# pmg001.net
KiCad netlist of a schematic drawn in EAGLE
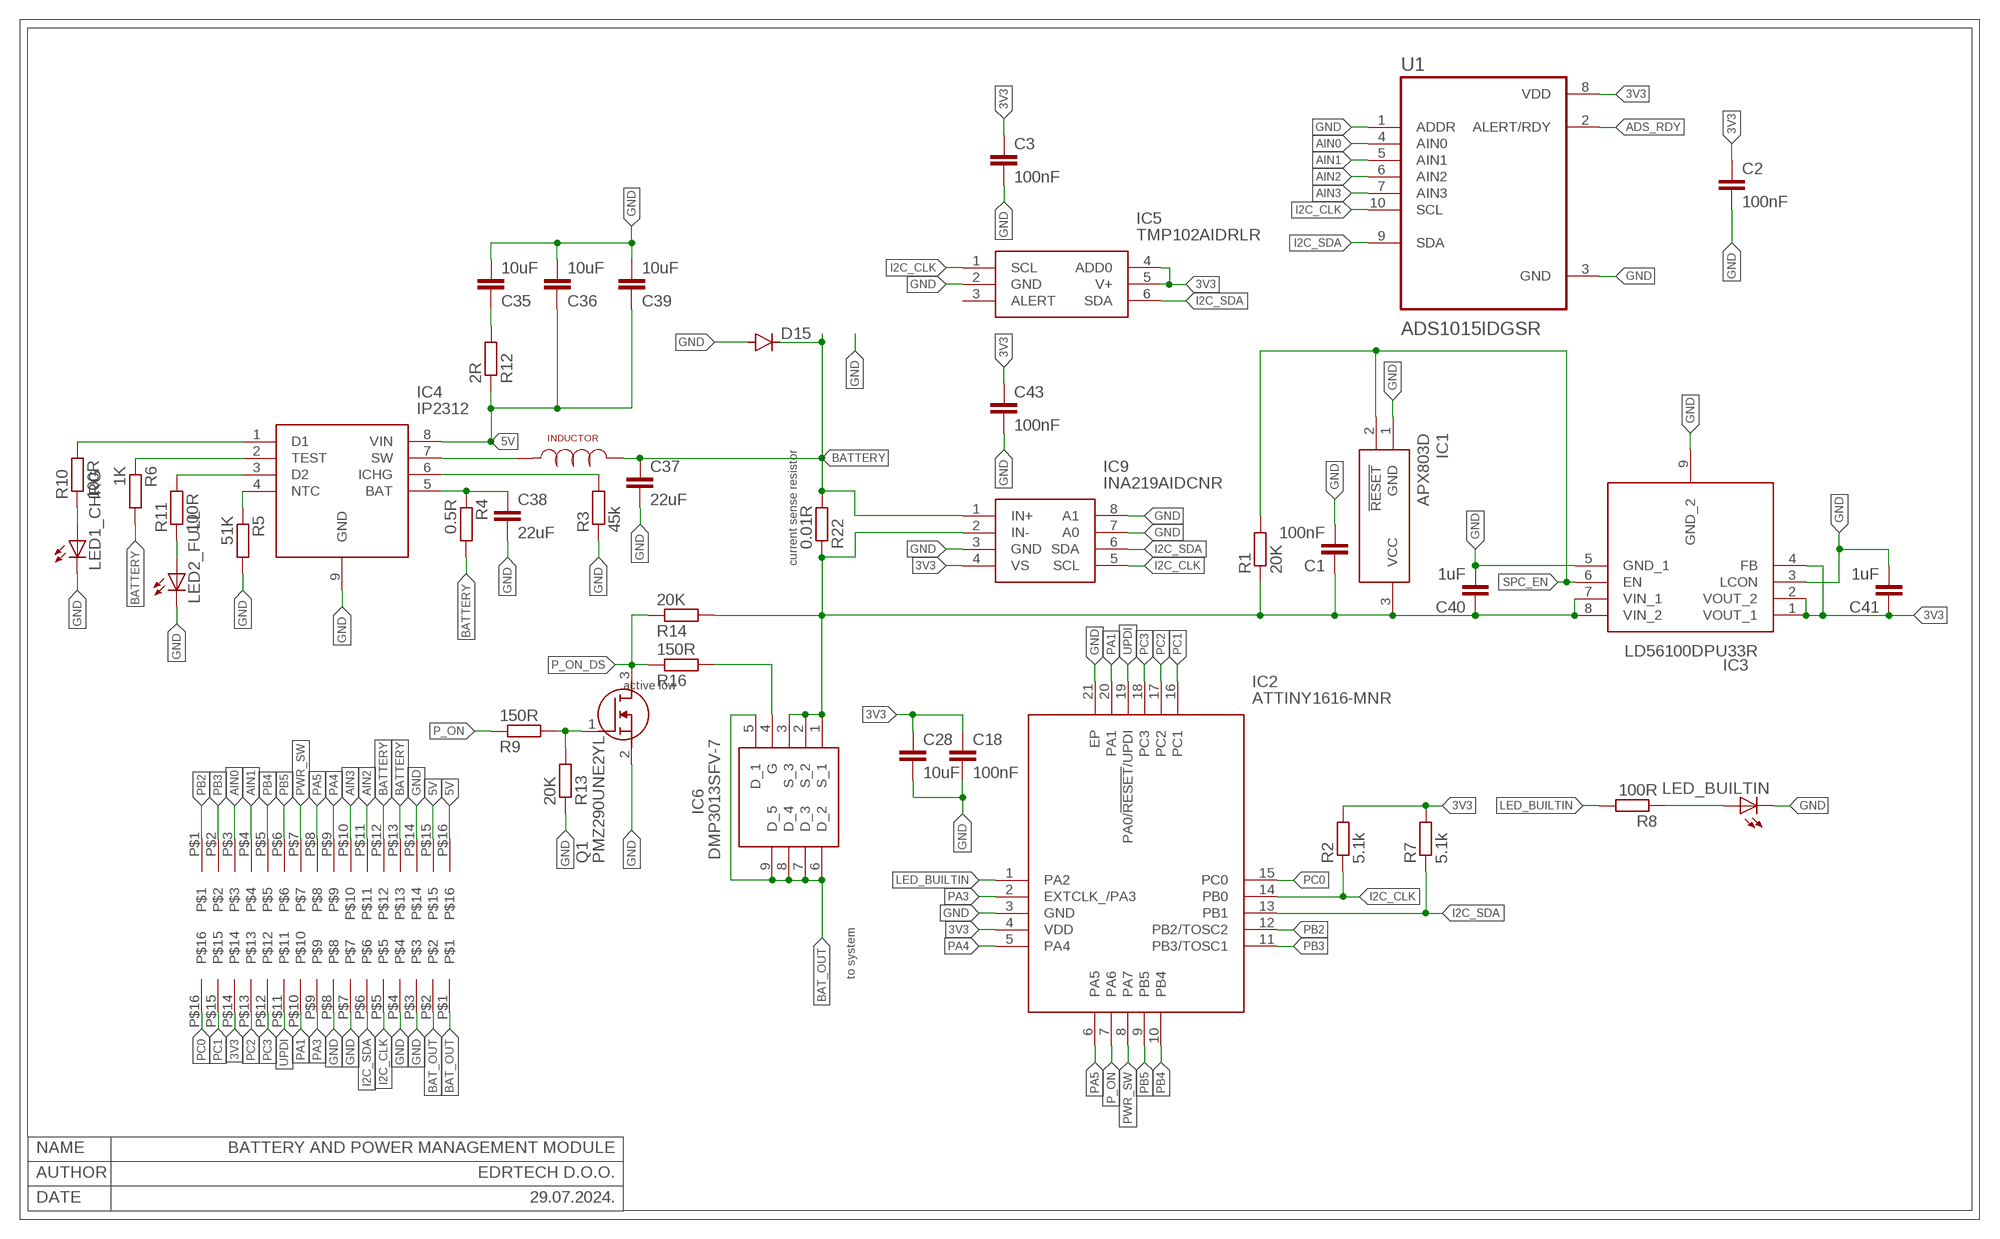
[diagram p0: schematic, sheet 1]

(export (version "E")
  (design (tool "Eeschema 10.0.6"))
  (components
    (comp (ref "C1")
      (value "100nF")
      (footprint "eagle-import:C0402")
      (libsource (lib "eagle-import") (part "C-EUC0402"))
    )
    (comp (ref "C2")
      (value "100nF")
      (footprint "eagle-import:C0402")
      (libsource (lib "eagle-import") (part "C-EUC0402"))
    )
    (comp (ref "C3")
      (value "100nF")
      (footprint "eagle-import:C0402")
      (libsource (lib "eagle-import") (part "C-EUC0402"))
    )
    (comp (ref "C18")
      (value "100nF")
      (footprint "eagle-import:C0402")
      (libsource (lib "eagle-import") (part "C-EUC0402"))
    )
    (comp (ref "C28")
      (value "10uF")
      (footprint "eagle-import:C0402")
      (libsource (lib "eagle-import") (part "C-EUC0402"))
    )
    (comp (ref "C35")
      (value "10uF")
      (footprint "eagle-import:C0603")
      (libsource (lib "eagle-import") (part "C-EUC0603"))
    )
    (comp (ref "C36")
      (value "10uF")
      (footprint "eagle-import:C0603")
      (libsource (lib "eagle-import") (part "C-EUC0603"))
    )
    (comp (ref "C37")
      (value "22uF")
      (footprint "eagle-import:C0603")
      (libsource (lib "eagle-import") (part "C-EUC0603"))
    )
    (comp (ref "C38")
      (value "22uF")
      (footprint "eagle-import:C0603")
      (libsource (lib "eagle-import") (part "C-EUC0603"))
    )
    (comp (ref "C39")
      (value "10uF")
      (footprint "eagle-import:C0603")
      (libsource (lib "eagle-import") (part "C-EUC0603"))
    )
    (comp (ref "C40")
      (value "1uF")
      (footprint "eagle-import:C0402")
      (libsource (lib "eagle-import") (part "C-EUC0402"))
    )
    (comp (ref "C41")
      (value "1uF")
      (footprint "eagle-import:C0402")
      (libsource (lib "eagle-import") (part "C-EUC0402"))
    )
    (comp (ref "C43")
      (value "100nF")
      (footprint "eagle-import:C0402")
      (libsource (lib "eagle-import") (part "C-EUC0402"))
    )
    (comp (ref "D15")
      (value "DIODE-SOD523")
      (footprint "eagle-import:SOD523")
      (libsource (lib "eagle-import") (part "DIODE-SOD523"))
    )
    (comp (ref "IC1")
      (value "APX803D-29SAG-7")
      (footprint "eagle-import:SOT96P240X110-3N")
      (fields (field (name "MOUSER_PART_NUMBER") "621-APX803D-29SAG-7"))
      (libsource (lib "eagle-import") (part "APX803D-29SAG-7"))
    )
    (comp (ref "IC2")
      (value "ATTINY1616-MNR")
      (footprint "eagle-import:QFN40P300X300X90-21N")
      (fields (field (name "MOUSER_PART_NUMBER") "556-ATTINY1616MNR"))
      (libsource (lib "eagle-import") (part "ATTINY1616-MNR"))
    )
    (comp (ref "IC3")
      (value "LD56100DPU30R")
      (footprint "eagle-import:SON40P120X160X50-9N")
      (fields (field (name "MOUSER_PART_NUMBER") "511-LD56100DPU30R"))
      (libsource (lib "eagle-import") (part "LD56100DPU30R"))
    )
    (comp (ref "IC4")
      (value "IP2312")
      (footprint "eagle-import:SOIC127P600X165-9N")
      (libsource (lib "eagle-import") (part "IP2312"))
    )
    (comp (ref "IC5")
      (value "TMP102AIDRLR")
      (footprint "eagle-import:SOTFL50P160X60-6N")
      (fields (field (name "MOUSER_PART_NUMBER") "595-TMP102AIDRLR"))
      (libsource (lib "eagle-import") (part "TMP102AIDRLR"))
    )
    (comp (ref "IC6")
      (value "DMP3013SFV-7")
      (footprint "eagle-import:DMP3036SFV7")
      (fields (field (name "MOUSER_PART_NUMBER") "621-DMP3013SFV-7"))
      (libsource (lib "eagle-import") (part "DMP3013SFV-7"))
    )
    (comp (ref "IC9")
      (value "INA219AIDCNR")
      (footprint "eagle-import:SOP65P280X145-8N")
      (fields (field (name "MOUSER_PART_NUMBER") "595-INA219AIDCNR"))
      (libsource (lib "eagle-import") (part "INA219AIDCNR"))
    )
    (comp (ref "LED1_CHRG")
      (value "LEDCHIPLED_0603")
      (footprint "eagle-import:CHIPLED_0603")
      (libsource (lib "eagle-import") (part "LEDCHIPLED_0603"))
    )
    (comp (ref "LED2_FULL")
      (value "LEDCHIPLED_0603")
      (footprint "eagle-import:CHIPLED_0603")
      (libsource (lib "eagle-import") (part "LEDCHIPLED_0603"))
    )
    (comp (ref "LED_BUILTIN")
      (value "LEDCHIPLED_0603")
      (footprint "eagle-import:CHIPLED_0603")
      (libsource (lib "eagle-import") (part "LEDCHIPLED_0603"))
    )
    (comp (ref "Q1")
      (value "PMZ290UNE2YL")
      (footprint "eagle-import:PMZ290UNE2YL")
      (fields (field (name "MOUSER_PART_NUMBER") "771-PMZ290UNE2YL"))
      (libsource (lib "eagle-import") (part "PMZ290UNE2YL"))
    )
    (comp (ref "R1")
      (value "20K")
      (footprint "eagle-import:R0402")
      (libsource (lib "eagle-import") (part "R-EU_R0402"))
    )
    (comp (ref "R2")
      (value "5.1k")
      (footprint "eagle-import:R0402")
      (libsource (lib "eagle-import") (part "R-EU_R0402"))
    )
    (comp (ref "R3")
      (value "45k")
      (footprint "eagle-import:R0402")
      (libsource (lib "eagle-import") (part "R-EU_R0402"))
    )
    (comp (ref "R4")
      (value "0.5R")
      (footprint "eagle-import:R0402")
      (libsource (lib "eagle-import") (part "R-EU_R0402"))
    )
    (comp (ref "R5")
      (value "51K")
      (footprint "eagle-import:R0402")
      (libsource (lib "eagle-import") (part "R-EU_R0402"))
    )
    (comp (ref "R6")
      (value "1K")
      (footprint "eagle-import:R0402")
      (libsource (lib "eagle-import") (part "R-EU_R0402"))
    )
    (comp (ref "R7")
      (value "5.1k")
      (footprint "eagle-import:R0402")
      (libsource (lib "eagle-import") (part "R-EU_R0402"))
    )
    (comp (ref "R8")
      (value "100R")
      (footprint "eagle-import:R0402")
      (libsource (lib "eagle-import") (part "R-EU_R0402"))
    )
    (comp (ref "R9")
      (value "150R")
      (footprint "eagle-import:R0402")
      (libsource (lib "eagle-import") (part "R-EU_R0402"))
    )
    (comp (ref "R10")
      (value "100R")
      (footprint "eagle-import:R0402")
      (libsource (lib "eagle-import") (part "R-EU_R0402"))
    )
    (comp (ref "R11")
      (value "100R")
      (footprint "eagle-import:R0402")
      (libsource (lib "eagle-import") (part "R-EU_R0402"))
    )
    (comp (ref "R12")
      (value "2R")
      (footprint "eagle-import:R0402")
      (libsource (lib "eagle-import") (part "R-EU_R0402"))
    )
    (comp (ref "R13")
      (value "20K")
      (footprint "eagle-import:R0402")
      (libsource (lib "eagle-import") (part "R-EU_R0402"))
    )
    (comp (ref "R14")
      (value "20K")
      (footprint "eagle-import:R0402")
      (libsource (lib "eagle-import") (part "R-EU_R0402"))
    )
    (comp (ref "R16")
      (value "150R")
      (footprint "eagle-import:R0402")
      (libsource (lib "eagle-import") (part "R-EU_R0402"))
    )
    (comp (ref "R22")
      (value "0.01R")
      (footprint "eagle-import:R2512")
      (libsource (lib "eagle-import") (part "R-EU_R2512"))
    )
    (comp (ref "U$1")
      (value "1.27_MALE_16P_HEADER")
      (footprint "eagle-import:1.27_MALE_16P_HEADER")
      (libsource (lib "eagle-import") (part "1.27_MALE_16P_HEADER"))
    )
    (comp (ref "U$2")
      (value "1.27_MALE_16P_HEADER")
      (footprint "eagle-import:1.27_MALE_16P_HEADER")
      (libsource (lib "eagle-import") (part "1.27_MALE_16P_HEADER"))
    )
    (comp (ref "U$91")
      (value "1uH")
      (footprint "eagle-import:NRS5040T3R3NMGJ")
      (libsource (lib "eagle-import") (part "NRS5040T3R3NMGJ"))
    )
    (comp (ref "U1")
      (value "ADS1015IDGSR")
      (footprint "eagle-import:SOP50P490X110-10N")
      (fields (field (name "MF") "Texas Instruments"))
      (libsource (lib "eagle-import") (part "ADS1015IDGSR"))
    )
  )
  (nets
    (net (code "1") (name "3V3") (class "Default")
      (node (ref "C18") (pin "1") (pinfunction "1_1") (pintype "passive"))
      (node (ref "C2") (pin "1") (pinfunction "1_1") (pintype "passive"))
      (node (ref "C28") (pin "1") (pinfunction "1_1") (pintype "passive"))
      (node (ref "C3") (pin "1") (pinfunction "1_1") (pintype "passive"))
      (node (ref "C41") (pin "1") (pinfunction "1_1") (pintype "passive"))
      (node (ref "C43") (pin "1") (pinfunction "1_1") (pintype "passive"))
      (node (ref "IC2") (pin "4") (pinfunction "VDD_4") (pintype "bidirectional"))
      (node (ref "IC3") (pin "1") (pinfunction "VOUT_1_1") (pintype "bidirectional"))
      (node (ref "IC3") (pin "2") (pinfunction "VOUT_2_2") (pintype "bidirectional"))
      (node (ref "IC3") (pin "4") (pinfunction "FB_4") (pintype "bidirectional"))
      (node (ref "IC5") (pin "4") (pinfunction "ADD0_4") (pintype "bidirectional"))
      (node (ref "IC5") (pin "5") (pinfunction "V+_5") (pintype "bidirectional"))
      (node (ref "IC9") (pin "4") (pinfunction "VS_4") (pintype "bidirectional"))
      (node (ref "R2") (pin "2") (pinfunction "2_2") (pintype "passive"))
      (node (ref "R7") (pin "2") (pinfunction "2_2") (pintype "passive"))
      (node (ref "U$2") (pin "P$14") (pinfunction "P$14_P$14") (pintype "bidirectional"))
      (node (ref "U1") (pin "8") (pinfunction "VDD_8") (pintype "power_in"))
    )
    (net (code "2") (name "5V") (class "Default")
      (node (ref "C36") (pin "1") (pinfunction "1_1") (pintype "passive"))
      (node (ref "C39") (pin "1") (pinfunction "1_1") (pintype "passive"))
      (node (ref "IC4") (pin "8") (pinfunction "VIN_8") (pintype "bidirectional"))
      (node (ref "R12") (pin "1") (pinfunction "1_1") (pintype "passive"))
      (node (ref "U$1") (pin "P$15") (pinfunction "P$15_P$15") (pintype "bidirectional"))
      (node (ref "U$1") (pin "P$16") (pinfunction "P$16_P$16") (pintype "bidirectional"))
    )
    (net (code "3") (name "ADS_RDY") (class "Default")
      (node (ref "U1") (pin "2") (pinfunction "ALERT/RDY_2") (pintype "output"))
    )
    (net (code "4") (name "AIN0") (class "Default")
      (node (ref "U$1") (pin "P$3") (pinfunction "P$3_P$3") (pintype "bidirectional"))
      (node (ref "U1") (pin "4") (pinfunction "AIN0_4") (pintype "input"))
    )
    (net (code "5") (name "AIN1") (class "Default")
      (node (ref "U$1") (pin "P$4") (pinfunction "P$4_P$4") (pintype "bidirectional"))
      (node (ref "U1") (pin "5") (pinfunction "AIN1_5") (pintype "input"))
    )
    (net (code "6") (name "AIN2") (class "Default")
      (node (ref "U$1") (pin "P$11") (pinfunction "P$11_P$11") (pintype "bidirectional"))
      (node (ref "U1") (pin "6") (pinfunction "AIN2_6") (pintype "input"))
    )
    (net (code "7") (name "AIN3") (class "Default")
      (node (ref "U$1") (pin "P$10") (pinfunction "P$10_P$10") (pintype "bidirectional"))
      (node (ref "U1") (pin "7") (pinfunction "AIN3_7") (pintype "input"))
    )
    (net (code "8") (name "BATTERY") (class "Default")
      (node (ref "C37") (pin "1") (pinfunction "1_1") (pintype "passive"))
      (node (ref "D15") (pin "C") (pinfunction "C_C") (pintype "passive"))
      (node (ref "IC9") (pin "1") (pinfunction "IN+_1") (pintype "bidirectional"))
      (node (ref "R22") (pin "2") (pinfunction "2_2") (pintype "passive"))
      (node (ref "R4") (pin "2") (pinfunction "2_2") (pintype "passive"))
      (node (ref "R6") (pin "2") (pinfunction "2_2") (pintype "passive"))
      (node (ref "U$1") (pin "P$12") (pinfunction "P$12_P$12") (pintype "bidirectional"))
      (node (ref "U$1") (pin "P$13") (pinfunction "P$13_P$13") (pintype "bidirectional"))
      (node (ref "U$91") (pin "P$1") (pinfunction "P$1_P$1") (pintype "bidirectional"))
    )
    (net (code "9") (name "BAT_OUT") (class "Default")
      (node (ref "IC6") (pin "5") (pinfunction "D_1_5") (pintype "bidirectional"))
      (node (ref "IC6") (pin "6") (pinfunction "D_2_6") (pintype "bidirectional"))
      (node (ref "IC6") (pin "7") (pinfunction "D_3_7") (pintype "bidirectional"))
      (node (ref "IC6") (pin "8") (pinfunction "D_4_8") (pintype "bidirectional"))
      (node (ref "IC6") (pin "9") (pinfunction "D_5_9") (pintype "bidirectional"))
      (node (ref "U$2") (pin "P$1") (pinfunction "P$1_P$1") (pintype "bidirectional"))
      (node (ref "U$2") (pin "P$2") (pinfunction "P$2_P$2") (pintype "bidirectional"))
    )
    (net (code "10") (name "GND") (class "Default")
      (node (ref "C1") (pin "2") (pinfunction "2_2") (pintype "passive"))
      (node (ref "C18") (pin "2") (pinfunction "2_2") (pintype "passive"))
      (node (ref "C2") (pin "2") (pinfunction "2_2") (pintype "passive"))
      (node (ref "C28") (pin "2") (pinfunction "2_2") (pintype "passive"))
      (node (ref "C3") (pin "2") (pinfunction "2_2") (pintype "passive"))
      (node (ref "C35") (pin "2") (pinfunction "2_2") (pintype "passive"))
      (node (ref "C36") (pin "2") (pinfunction "2_2") (pintype "passive"))
      (node (ref "C37") (pin "2") (pinfunction "2_2") (pintype "passive"))
      (node (ref "C38") (pin "2") (pinfunction "2_2") (pintype "passive"))
      (node (ref "C39") (pin "2") (pinfunction "2_2") (pintype "passive"))
      (node (ref "C40") (pin "2") (pinfunction "2_2") (pintype "passive"))
      (node (ref "C41") (pin "2") (pinfunction "2_2") (pintype "passive"))
      (node (ref "C43") (pin "2") (pinfunction "2_2") (pintype "passive"))
      (node (ref "D15") (pin "A") (pinfunction "A_A") (pintype "passive"))
      (node (ref "IC1") (pin "1") (pinfunction "GND_1") (pintype "bidirectional"))
      (node (ref "IC2") (pin "21") (pinfunction "EP_21") (pintype "bidirectional"))
      (node (ref "IC2") (pin "3") (pinfunction "GND_3") (pintype "bidirectional"))
      (node (ref "IC3") (pin "3") (pinfunction "LCON_3") (pintype "bidirectional"))
      (node (ref "IC3") (pin "5") (pinfunction "GND_1_5") (pintype "bidirectional"))
      (node (ref "IC3") (pin "9") (pinfunction "GND_2_9") (pintype "bidirectional"))
      (node (ref "IC4") (pin "9") (pinfunction "GND_9") (pintype "bidirectional"))
      (node (ref "IC5") (pin "2") (pinfunction "GND_2") (pintype "bidirectional"))
      (node (ref "IC9") (pin "3") (pinfunction "GND_3") (pintype "bidirectional"))
      (node (ref "IC9") (pin "7") (pinfunction "A0_7") (pintype "bidirectional"))
      (node (ref "IC9") (pin "8") (pinfunction "A1_8") (pintype "bidirectional"))
      (node (ref "LED1_CHRG") (pin "C") (pinfunction "C_C") (pintype "passive"))
      (node (ref "LED2_FULL") (pin "C") (pinfunction "C_C") (pintype "passive"))
      (node (ref "LED_BUILTIN") (pin "C") (pinfunction "C_C") (pintype "passive"))
      (node (ref "Q1") (pin "2") (pinfunction "S_2") (pintype "bidirectional"))
      (node (ref "R13") (pin "1") (pinfunction "1_1") (pintype "passive"))
      (node (ref "R3") (pin "1") (pinfunction "1_1") (pintype "passive"))
      (node (ref "R5") (pin "2") (pinfunction "2_2") (pintype "passive"))
      (node (ref "U$1") (pin "P$14") (pinfunction "P$14_P$14") (pintype "bidirectional"))
      (node (ref "U$2") (pin "P$3") (pinfunction "P$3_P$3") (pintype "bidirectional"))
      (node (ref "U$2") (pin "P$4") (pinfunction "P$4_P$4") (pintype "bidirectional"))
      (node (ref "U$2") (pin "P$7") (pinfunction "P$7_P$7") (pintype "bidirectional"))
      (node (ref "U$2") (pin "P$8") (pinfunction "P$8_P$8") (pintype "bidirectional"))
      (node (ref "U1") (pin "1") (pinfunction "ADDR_1") (pintype "input"))
      (node (ref "U1") (pin "3") (pinfunction "GND_3") (pintype "power_in"))
    )
    (net (code "11") (name "I2C_CLK") (class "Default")
      (node (ref "IC2") (pin "14") (pinfunction "PB0_14") (pintype "bidirectional"))
      (node (ref "IC5") (pin "1") (pinfunction "SCL_1") (pintype "bidirectional"))
      (node (ref "IC9") (pin "5") (pinfunction "SCL_5") (pintype "bidirectional"))
      (node (ref "R2") (pin "1") (pinfunction "1_1") (pintype "passive"))
      (node (ref "U$2") (pin "P$5") (pinfunction "P$5_P$5") (pintype "bidirectional"))
      (node (ref "U1") (pin "10") (pinfunction "SCL_10") (pintype "input"))
    )
    (net (code "12") (name "I2C_SDA") (class "Default")
      (node (ref "IC2") (pin "13") (pinfunction "PB1_13") (pintype "bidirectional"))
      (node (ref "IC5") (pin "6") (pinfunction "SDA_6") (pintype "bidirectional"))
      (node (ref "IC9") (pin "6") (pinfunction "SDA_6") (pintype "bidirectional"))
      (node (ref "R7") (pin "1") (pinfunction "1_1") (pintype "passive"))
      (node (ref "U$2") (pin "P$6") (pinfunction "P$6_P$6") (pintype "bidirectional"))
      (node (ref "U1") (pin "9") (pinfunction "SDA_9") (pintype "bidirectional"))
    )
    (net (code "13") (name "LED_BUILTIN") (class "Default")
      (node (ref "IC2") (pin "1") (pinfunction "PA2_1") (pintype "bidirectional"))
      (node (ref "R8") (pin "2") (pinfunction "2_2") (pintype "passive"))
    )
    (net (code "14") (name "Net-(C35-Pad1)") (class "Default")
      (node (ref "C35") (pin "1") (pinfunction "1_1") (pintype "passive"))
      (node (ref "R12") (pin "2") (pinfunction "2_2") (pintype "passive"))
    )
    (net (code "15") (name "Net-(IC1-VCC)") (class "Default")
      (node (ref "C1") (pin "1") (pinfunction "1_1") (pintype "passive"))
      (node (ref "C40") (pin "1") (pinfunction "1_1") (pintype "passive"))
      (node (ref "IC1") (pin "3") (pinfunction "VCC_3") (pintype "bidirectional"))
      (node (ref "IC3") (pin "7") (pinfunction "VIN_1_7") (pintype "bidirectional"))
      (node (ref "IC3") (pin "8") (pinfunction "VIN_2_8") (pintype "bidirectional"))
      (node (ref "IC6") (pin "1") (pinfunction "S_1_1") (pintype "bidirectional"))
      (node (ref "IC6") (pin "2") (pinfunction "S_2_2") (pintype "bidirectional"))
      (node (ref "IC6") (pin "3") (pinfunction "S_3_3") (pintype "bidirectional"))
      (node (ref "IC9") (pin "2") (pinfunction "IN-_2") (pintype "bidirectional"))
      (node (ref "R1") (pin "1") (pinfunction "1_1") (pintype "passive"))
      (node (ref "R14") (pin "2") (pinfunction "2_2") (pintype "passive"))
      (node (ref "R22") (pin "1") (pinfunction "1_1") (pintype "passive"))
    )
    (net (code "16") (name "Net-(IC4-BAT)") (class "Default")
      (node (ref "C38") (pin "1") (pinfunction "1_1") (pintype "passive"))
      (node (ref "IC4") (pin "5") (pinfunction "BAT_5") (pintype "bidirectional"))
      (node (ref "R4") (pin "1") (pinfunction "1_1") (pintype "passive"))
    )
    (net (code "17") (name "Net-(IC4-D1)") (class "Default")
      (node (ref "IC4") (pin "1") (pinfunction "D1_1") (pintype "bidirectional"))
      (node (ref "R10") (pin "2") (pinfunction "2_2") (pintype "passive"))
    )
    (net (code "18") (name "Net-(IC4-D2)") (class "Default")
      (node (ref "IC4") (pin "3") (pinfunction "D2_3") (pintype "bidirectional"))
      (node (ref "R11") (pin "2") (pinfunction "2_2") (pintype "passive"))
    )
    (net (code "19") (name "Net-(IC4-ICHG)") (class "Default")
      (node (ref "IC4") (pin "6") (pinfunction "ICHG_6") (pintype "bidirectional"))
      (node (ref "R3") (pin "2") (pinfunction "2_2") (pintype "passive"))
    )
    (net (code "20") (name "Net-(IC4-NTC)") (class "Default")
      (node (ref "IC4") (pin "4") (pinfunction "NTC_4") (pintype "bidirectional"))
      (node (ref "R5") (pin "1") (pinfunction "1_1") (pintype "passive"))
    )
    (net (code "21") (name "Net-(IC4-SW)") (class "Default")
      (node (ref "IC4") (pin "7") (pinfunction "SW_7") (pintype "bidirectional"))
      (node (ref "U$91") (pin "P$2") (pinfunction "P$2_P$2") (pintype "bidirectional"))
    )
    (net (code "22") (name "Net-(IC4-TEST)") (class "Default")
      (node (ref "IC4") (pin "2") (pinfunction "TEST_2") (pintype "bidirectional"))
      (node (ref "R6") (pin "1") (pinfunction "1_1") (pintype "passive"))
    )
    (net (code "23") (name "Net-(IC6-G)") (class "Default")
      (node (ref "IC6") (pin "4") (pinfunction "G_4") (pintype "bidirectional"))
      (node (ref "R16") (pin "2") (pinfunction "2_2") (pintype "passive"))
    )
    (net (code "24") (name "Net-(LED1_CHRG-PadA)") (class "Default")
      (node (ref "LED1_CHRG") (pin "A") (pinfunction "A_A") (pintype "passive"))
      (node (ref "R10") (pin "1") (pinfunction "1_1") (pintype "passive"))
    )
    (net (code "25") (name "Net-(LED2_FULL-PadA)") (class "Default")
      (node (ref "LED2_FULL") (pin "A") (pinfunction "A_A") (pintype "passive"))
      (node (ref "R11") (pin "1") (pinfunction "1_1") (pintype "passive"))
    )
    (net (code "26") (name "Net-(LED_BUILTIN-PadA)") (class "Default")
      (node (ref "LED_BUILTIN") (pin "A") (pinfunction "A_A") (pintype "passive"))
      (node (ref "R8") (pin "1") (pinfunction "1_1") (pintype "passive"))
    )
    (net (code "27") (name "Net-(Q1-G)") (class "Default")
      (node (ref "Q1") (pin "1") (pinfunction "G_1") (pintype "bidirectional"))
      (node (ref "R13") (pin "2") (pinfunction "2_2") (pintype "passive"))
      (node (ref "R9") (pin "2") (pinfunction "2_2") (pintype "passive"))
    )
    (net (code "28") (name "PA1") (class "Default")
      (node (ref "IC2") (pin "20") (pinfunction "PA1_20") (pintype "bidirectional"))
      (node (ref "U$2") (pin "P$10") (pinfunction "P$10_P$10") (pintype "bidirectional"))
    )
    (net (code "29") (name "PA3") (class "Default")
      (node (ref "IC2") (pin "2") (pinfunction "EXTCLK_/PA3_2") (pintype "bidirectional"))
      (node (ref "U$2") (pin "P$9") (pinfunction "P$9_P$9") (pintype "bidirectional"))
    )
    (net (code "30") (name "PA4") (class "Default")
      (node (ref "IC2") (pin "5") (pinfunction "PA4_5") (pintype "bidirectional"))
      (node (ref "U$1") (pin "P$9") (pinfunction "P$9_P$9") (pintype "bidirectional"))
    )
    (net (code "31") (name "PA5") (class "Default")
      (node (ref "IC2") (pin "6") (pinfunction "PA5_6") (pintype "bidirectional"))
      (node (ref "U$1") (pin "P$8") (pinfunction "P$8_P$8") (pintype "bidirectional"))
    )
    (net (code "32") (name "PB2") (class "Default")
      (node (ref "IC2") (pin "12") (pinfunction "PB2/TOSC2_12") (pintype "bidirectional"))
      (node (ref "U$1") (pin "P$1") (pinfunction "P$1_P$1") (pintype "bidirectional"))
    )
    (net (code "33") (name "PB3") (class "Default")
      (node (ref "IC2") (pin "11") (pinfunction "PB3/TOSC1_11") (pintype "bidirectional"))
      (node (ref "U$1") (pin "P$2") (pinfunction "P$2_P$2") (pintype "bidirectional"))
    )
    (net (code "34") (name "PB4") (class "Default")
      (node (ref "IC2") (pin "10") (pinfunction "PB4_10") (pintype "bidirectional"))
      (node (ref "U$1") (pin "P$5") (pinfunction "P$5_P$5") (pintype "bidirectional"))
    )
    (net (code "35") (name "PB5") (class "Default")
      (node (ref "IC2") (pin "9") (pinfunction "PB5_9") (pintype "bidirectional"))
      (node (ref "U$1") (pin "P$6") (pinfunction "P$6_P$6") (pintype "bidirectional"))
    )
    (net (code "36") (name "PC0") (class "Default")
      (node (ref "IC2") (pin "15") (pinfunction "PC0_15") (pintype "bidirectional"))
      (node (ref "U$2") (pin "P$16") (pinfunction "P$16_P$16") (pintype "bidirectional"))
    )
    (net (code "37") (name "PC1") (class "Default")
      (node (ref "IC2") (pin "16") (pinfunction "PC1_16") (pintype "bidirectional"))
      (node (ref "U$2") (pin "P$15") (pinfunction "P$15_P$15") (pintype "bidirectional"))
    )
    (net (code "38") (name "PC2") (class "Default")
      (node (ref "IC2") (pin "17") (pinfunction "PC2_17") (pintype "bidirectional"))
      (node (ref "U$2") (pin "P$13") (pinfunction "P$13_P$13") (pintype "bidirectional"))
    )
    (net (code "39") (name "PC3") (class "Default")
      (node (ref "IC2") (pin "18") (pinfunction "PC3_18") (pintype "bidirectional"))
      (node (ref "U$2") (pin "P$12") (pinfunction "P$12_P$12") (pintype "bidirectional"))
    )
    (net (code "40") (name "PWR_SW") (class "Default")
      (node (ref "IC2") (pin "8") (pinfunction "PA7_8") (pintype "bidirectional"))
      (node (ref "U$1") (pin "P$7") (pinfunction "P$7_P$7") (pintype "bidirectional"))
    )
    (net (code "41") (name "P_ON") (class "Default")
      (node (ref "IC2") (pin "7") (pinfunction "PA6_7") (pintype "bidirectional"))
      (node (ref "R9") (pin "1") (pinfunction "1_1") (pintype "passive"))
    )
    (net (code "42") (name "P_ON_DS") (class "Default")
      (node (ref "Q1") (pin "3") (pinfunction "D_3") (pintype "bidirectional"))
      (node (ref "R14") (pin "1") (pinfunction "1_1") (pintype "passive"))
      (node (ref "R16") (pin "1") (pinfunction "1_1") (pintype "passive"))
    )
    (net (code "43") (name "SPC_EN") (class "Default")
      (node (ref "IC1") (pin "2") (pinfunction "~{RESET}_2") (pintype "bidirectional"))
      (node (ref "IC3") (pin "6") (pinfunction "EN_6") (pintype "bidirectional"))
      (node (ref "R1") (pin "2") (pinfunction "2_2") (pintype "passive"))
    )
    (net (code "44") (name "UPDI") (class "Default")
      (node (ref "IC2") (pin "19") (pinfunction "PA0/~{RESET}/UPDI_19") (pintype "bidirectional"))
      (node (ref "U$2") (pin "P$11") (pinfunction "P$11_P$11") (pintype "bidirectional"))
    )
    (net (code "45") (name "unconnected-(IC5-ALERT-Pad3)") (class "Default")
      (node (ref "IC5") (pin "3") (pinfunction "ALERT_3") (pintype "bidirectional"))
    )
  )
)
